# METEOR2K17_final.net
KiCad netlist of a schematic drawn in EAGLE
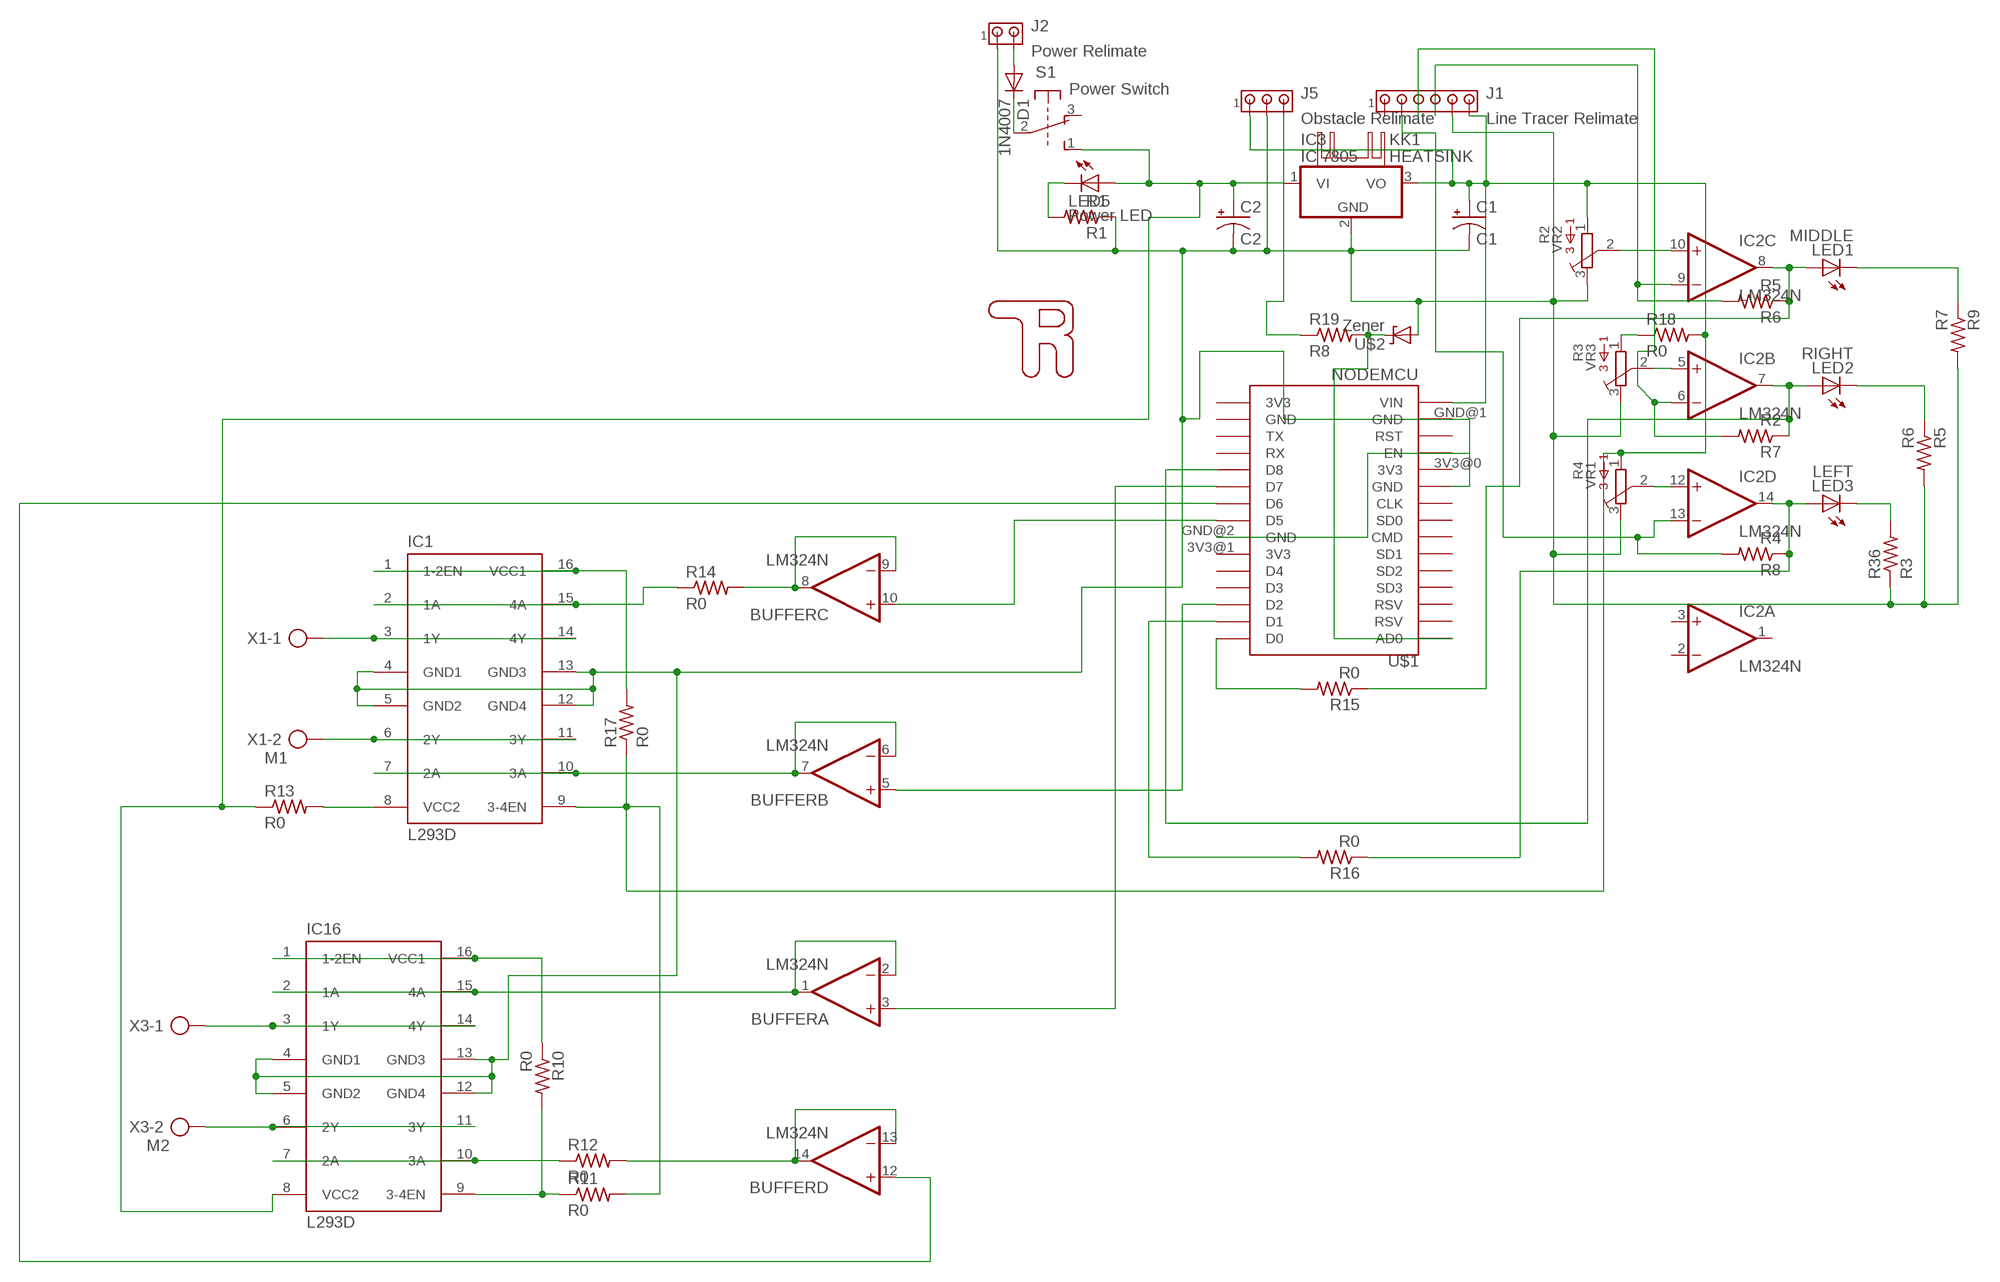
[diagram p0: schematic, sheet 1]

(export (version "E")
  (design (tool "Eeschema 10.0.6"))
  (components
    (comp (ref "BUFFER")
      (value "LM324N")
      (footprint "eagle-import:DIL14")
      (libsource (lib "eagle-import") (part "LM324N"))
    )
    (comp (ref "C1")
      (value "C1")
      (footprint "eagle-import:CPOL-RADIAL-5MM-10MM")
      (libsource (lib "eagle-import") (part "1000UF-RADIAL-5MM-25V-20%"))
    )
    (comp (ref "C2")
      (value "C2")
      (footprint "eagle-import:E3,5-8")
      (libsource (lib "eagle-import") (part "CPOL-USE3.5-8"))
    )
    (comp (ref "D1")
      (value "1N4007")
      (footprint "eagle-import:DO41-10")
      (libsource (lib "eagle-import") (part "1N4004"))
    )
    (comp (ref "IC1")
      (value "L293D")
      (footprint "eagle-import:DIL16")
      (libsource (lib "eagle-import") (part "L293D"))
    )
    (comp (ref "IC2")
      (value "LM324N")
      (footprint "eagle-import:DIL14")
      (libsource (lib "eagle-import") (part "LM324N"))
    )
    (comp (ref "IC3")
      (value "IC 7805")
      (footprint "eagle-import:TO220V")
      (libsource (lib "eagle-import") (part "78TV05"))
    )
    (comp (ref "IC16")
      (value "L293D")
      (footprint "eagle-import:DIL16")
      (libsource (lib "eagle-import") (part "L293D"))
    )
    (comp (ref "J1")
      (value "Line Tracer Relimate")
      (footprint "eagle-import:10X06MTA")
      (libsource (lib "eagle-import") (part "MTA06-100"))
    )
    (comp (ref "J2")
      (value "Power Relimate")
      (footprint "eagle-import:10X02MTA")
      (libsource (lib "eagle-import") (part "MTA02-100"))
    )
    (comp (ref "J5")
      (value "Obstacle Relimate")
      (footprint "eagle-import:10X03MTA")
      (libsource (lib "eagle-import") (part "MTA03-100"))
    )
    (comp (ref "KK1")
      (value "HEATSINK")
      (footprint "eagle-import:HEATSINK")
      (libsource (lib "eagle-import") (part "HEATSINK"))
    )
    (comp (ref "LED1")
      (value "MIDDLE")
      (footprint "eagle-import:LED3MM")
      (libsource (lib "eagle-import") (part "LED3MM"))
    )
    (comp (ref "LED2")
      (value "RIGHT")
      (footprint "eagle-import:LED3MM")
      (libsource (lib "eagle-import") (part "LED3MM"))
    )
    (comp (ref "LED3")
      (value "LEFT")
      (footprint "eagle-import:LED3MM")
      (libsource (lib "eagle-import") (part "LED3MM"))
    )
    (comp (ref "LED5")
      (value "Power LED")
      (footprint "eagle-import:LED3MM")
      (libsource (lib "eagle-import") (part "LED3MM"))
    )
    (comp (ref "R1")
      (value "R1")
      (footprint "eagle-import:0204_7")
      (libsource (lib "eagle-import") (part "R-US_0204/7"))
    )
    (comp (ref "R2")
      (value "VR2")
      (footprint "eagle-import:3386W")
      (libsource (lib "eagle-import") (part "3386-W"))
    )
    (comp (ref "R3")
      (value "VR3")
      (footprint "eagle-import:3386W")
      (libsource (lib "eagle-import") (part "3386-W"))
    )
    (comp (ref "R4")
      (value "VR1")
      (footprint "eagle-import:3386W")
      (libsource (lib "eagle-import") (part "3386-W"))
    )
    (comp (ref "R5")
      (value "R6")
      (footprint "eagle-import:0204_7")
      (libsource (lib "eagle-import") (part "R-US_0204/7"))
    )
    (comp (ref "R6")
      (value "R5")
      (footprint "eagle-import:0204_7")
      (libsource (lib "eagle-import") (part "R-US_0204/7"))
    )
    (comp (ref "R7")
      (value "R2")
      (footprint "eagle-import:0204_7")
      (libsource (lib "eagle-import") (part "R-US_0204/7"))
    )
    (comp (ref "R8")
      (value "R4")
      (footprint "eagle-import:0204_7")
      (libsource (lib "eagle-import") (part "R-US_0204/7"))
    )
    (comp (ref "R9")
      (value "R7")
      (footprint "eagle-import:0204_7")
      (libsource (lib "eagle-import") (part "R-US_0204/7"))
    )
    (comp (ref "R10")
      (value "R0")
      (footprint "eagle-import:0204_7")
      (libsource (lib "eagle-import") (part "R-US_0204/7"))
    )
    (comp (ref "R11")
      (value "R0")
      (footprint "eagle-import:0204_7")
      (libsource (lib "eagle-import") (part "R-US_0204/7"))
    )
    (comp (ref "R12")
      (value "R0")
      (footprint "eagle-import:0207_10")
      (libsource (lib "eagle-import") (part "R-US_0207/10"))
    )
    (comp (ref "R13")
      (value "R0")
      (footprint "eagle-import:0204_7")
      (libsource (lib "eagle-import") (part "R-US_0204/7"))
    )
    (comp (ref "R14")
      (value "R0")
      (footprint "eagle-import:0207_12")
      (libsource (lib "eagle-import") (part "R-US_0207/12"))
    )
    (comp (ref "R15")
      (value "R0")
      (footprint "eagle-import:0204_7")
      (libsource (lib "eagle-import") (part "R-US_0204/7"))
    )
    (comp (ref "R16")
      (value "R0")
      (footprint "eagle-import:0204_7")
      (libsource (lib "eagle-import") (part "R-US_0204/7"))
    )
    (comp (ref "R17")
      (value "R0")
      (footprint "eagle-import:0204_7")
      (libsource (lib "eagle-import") (part "R-US_0204/7"))
    )
    (comp (ref "R18")
      (value "R0")
      (footprint "eagle-import:0204_7")
      (libsource (lib "eagle-import") (part "R-US_0204/7"))
    )
    (comp (ref "R19")
      (value "R8")
      (footprint "eagle-import:0204_7")
      (libsource (lib "eagle-import") (part "R-US_0204/7"))
    )
    (comp (ref "R36")
      (value "R3")
      (footprint "eagle-import:0204_7")
      (libsource (lib "eagle-import") (part "R-US_0204/7"))
    )
    (comp (ref "S1")
      (value "Power Switch")
      (footprint "eagle-import:9077-2")
      (libsource (lib "eagle-import") (part "9077-2"))
    )
    (comp (ref "U$1")
      (value "NODEMCU")
      (footprint "eagle-import:NODEMCU_HSILK")
      (libsource (lib "eagle-import") (part "NODEMCU_V20"))
    )
    (comp (ref "U$2")
      (value "Zener")
      (footprint "eagle-import:DIODE-ZENER")
      (libsource (lib "eagle-import") (part "DIODE-ZENERPTH"))
    )
    (comp (ref "U$3")
      (value "TRLOGO")
      (footprint "eagle-import:TRLOGO")
      (libsource (lib "eagle-import") (part "TRLOGO"))
    )
    (comp (ref "X1")
      (value "M1")
      (footprint "eagle-import:AK300_2")
      (libsource (lib "eagle-import") (part "AK300/2"))
    )
    (comp (ref "X3")
      (value "M2")
      (footprint "eagle-import:AK300_2")
      (libsource (lib "eagle-import") (part "AK300/2"))
    )
  )
  (nets
    (net (code "1") (name "/5V") (class "Default")
      (node (ref "C1") (pin "+") (pinfunction "+_+") (pintype "passive"))
      (node (ref "IC1") (pin "1") (pinfunction "1-2EN_1") (pintype "input"))
      (node (ref "IC1") (pin "16") (pinfunction "VCC1_16") (pintype "power_in"))
      (node (ref "IC1") (pin "9") (pinfunction "3-4EN_9") (pintype "input"))
      (node (ref "IC16") (pin "1") (pinfunction "1-2EN_1") (pintype "input"))
      (node (ref "IC16") (pin "16") (pinfunction "VCC1_16") (pintype "power_in"))
      (node (ref "IC16") (pin "9") (pinfunction "3-4EN_9") (pintype "input"))
      (node (ref "IC3") (pin "3") (pinfunction "VO_3") (pintype "passive"))
      (node (ref "J1") (pin "1") (pinfunction "6_1") (pintype "passive"))
      (node (ref "J5") (pin "1") (pinfunction "1_1") (pintype "passive"))
      (node (ref "R10") (pin "1") (pinfunction "1_1") (pintype "passive"))
      (node (ref "R10") (pin "2") (pinfunction "2_2") (pintype "passive"))
      (node (ref "R11") (pin "1") (pinfunction "1_1") (pintype "passive"))
      (node (ref "R11") (pin "2") (pinfunction "2_2") (pintype "passive"))
      (node (ref "R17") (pin "1") (pinfunction "1_1") (pintype "passive"))
      (node (ref "R17") (pin "2") (pinfunction "2_2") (pintype "passive"))
      (node (ref "R18") (pin "2") (pinfunction "2_2") (pintype "passive"))
      (node (ref "R2") (pin "1") (pinfunction "1_1") (pintype "passive"))
      (node (ref "R4") (pin "1") (pinfunction "1_1") (pintype "passive"))
      (node (ref "U$1") (pin "VIN") (pinfunction "VIN_VIN") (pintype "bidirectional"))
    )
    (net (code "2") (name "/12V") (class "Default")
      (node (ref "C2") (pin "+") (pinfunction "+_+") (pintype "passive"))
      (node (ref "IC1") (pin "8") (pinfunction "VCC2_8") (pintype "power_in"))
      (node (ref "IC16") (pin "8") (pinfunction "VCC2_8") (pintype "power_in"))
      (node (ref "IC3") (pin "1") (pinfunction "VI_1") (pintype "input"))
      (node (ref "LED5") (pin "A") (pinfunction "A_A") (pintype "passive"))
      (node (ref "R13") (pin "1") (pinfunction "1_1") (pintype "passive"))
      (node (ref "R13") (pin "2") (pinfunction "2_2") (pintype "passive"))
      (node (ref "S1") (pin "1") (pinfunction "S_1") (pintype "passive"))
    )
    (net (code "3") (name "Net-(BUFFERA-+IN)") (class "Default")
      (node (ref "BUFFER") (pin "3") (pinfunction "+IN_3") (pintype "input"))
      (node (ref "U$1") (pin "D7") (pinfunction "D7_D7") (pintype "bidirectional"))
    )
    (net (code "4") (name "Net-(BUFFERA--IN)") (class "Default")
      (node (ref "BUFFER") (pin "1") (pinfunction "OUT_1") (pintype "output"))
      (node (ref "BUFFER") (pin "2") (pinfunction "-IN_2") (pintype "input"))
      (node (ref "IC16") (pin "15") (pinfunction "4A_15") (pintype "input"))
      (node (ref "IC16") (pin "2") (pinfunction "1A_2") (pintype "input"))
    )
    (net (code "5") (name "Net-(BUFFERB-+IN)") (class "Default")
      (node (ref "BUFFER") (pin "5") (pinfunction "+IN_5") (pintype "input"))
      (node (ref "U$1") (pin "D2") (pinfunction "D2_D2") (pintype "bidirectional"))
    )
    (net (code "6") (name "Net-(BUFFERB--IN)") (class "Default")
      (node (ref "BUFFER") (pin "6") (pinfunction "-IN_6") (pintype "input"))
      (node (ref "BUFFER") (pin "7") (pinfunction "OUT_7") (pintype "output"))
      (node (ref "IC1") (pin "10") (pinfunction "3A_10") (pintype "input"))
      (node (ref "IC1") (pin "7") (pinfunction "2A_7") (pintype "input"))
    )
    (net (code "7") (name "Net-(BUFFERC-+IN)") (class "Default")
      (node (ref "BUFFER") (pin "10") (pinfunction "+IN_10") (pintype "input"))
      (node (ref "U$1") (pin "D5") (pinfunction "D5_D5") (pintype "bidirectional"))
    )
    (net (code "8") (name "Net-(BUFFERC--IN)") (class "Default")
      (node (ref "BUFFER") (pin "8") (pinfunction "OUT_8") (pintype "output"))
      (node (ref "BUFFER") (pin "9") (pinfunction "-IN_9") (pintype "input"))
      (node (ref "R14") (pin "2") (pinfunction "2_2") (pintype "passive"))
    )
    (net (code "9") (name "Net-(BUFFERD-+IN)") (class "Default")
      (node (ref "BUFFER") (pin "12") (pinfunction "+IN_12") (pintype "input"))
      (node (ref "U$1") (pin "D6") (pinfunction "D6_D6") (pintype "bidirectional"))
    )
    (net (code "10") (name "Net-(BUFFERD--IN)") (class "Default")
      (node (ref "BUFFER") (pin "13") (pinfunction "-IN_13") (pintype "input"))
      (node (ref "BUFFER") (pin "14") (pinfunction "OUT_14") (pintype "output"))
      (node (ref "R12") (pin "2") (pinfunction "2_2") (pintype "passive"))
    )
    (net (code "11") (name "Net-(D1-PadA)") (class "Default")
      (node (ref "D1") (pin "A") (pinfunction "A_A") (pintype "passive"))
      (node (ref "J2") (pin "2") (pinfunction "2_2") (pintype "passive"))
    )
    (net (code "12") (name "Net-(IC1-1A)") (class "Default")
      (node (ref "IC1") (pin "15") (pinfunction "4A_15") (pintype "input"))
      (node (ref "IC1") (pin "2") (pinfunction "1A_2") (pintype "input"))
      (node (ref "R14") (pin "1") (pinfunction "1_1") (pintype "passive"))
    )
    (net (code "13") (name "Net-(IC1-1Y)") (class "Default")
      (node (ref "IC1") (pin "14") (pinfunction "4Y_14") (pintype "output"))
      (node (ref "IC1") (pin "3") (pinfunction "1Y_3") (pintype "output"))
      (node (ref "X1") (pin "1") (pinfunction "KL_1") (pintype "passive"))
    )
    (net (code "14") (name "Net-(IC1-2Y)") (class "Default")
      (node (ref "IC1") (pin "11") (pinfunction "3Y_11") (pintype "output"))
      (node (ref "IC1") (pin "6") (pinfunction "2Y_6") (pintype "output"))
      (node (ref "X1") (pin "2") (pinfunction "KL_2") (pintype "passive"))
    )
    (net (code "15") (name "Net-(IC1-GND1)") (class "Default")
      (node (ref "C1") (pin "-") (pinfunction "-_-") (pintype "passive"))
      (node (ref "C2") (pin "-") (pinfunction "-_-") (pintype "passive"))
      (node (ref "IC1") (pin "12") (pinfunction "GND4_12") (pintype "power_in"))
      (node (ref "IC1") (pin "13") (pinfunction "GND3_13") (pintype "power_in"))
      (node (ref "IC1") (pin "4") (pinfunction "GND1_4") (pintype "power_in"))
      (node (ref "IC1") (pin "5") (pinfunction "GND2_5") (pintype "power_in"))
      (node (ref "IC16") (pin "12") (pinfunction "GND4_12") (pintype "power_in"))
      (node (ref "IC16") (pin "13") (pinfunction "GND3_13") (pintype "power_in"))
      (node (ref "IC16") (pin "4") (pinfunction "GND1_4") (pintype "power_in"))
      (node (ref "IC16") (pin "5") (pinfunction "GND2_5") (pintype "power_in"))
      (node (ref "IC3") (pin "2") (pinfunction "GND_2") (pintype "passive"))
      (node (ref "J1") (pin "2") (pinfunction "5_2") (pintype "passive"))
      (node (ref "J2") (pin "1") (pinfunction "1_1") (pintype "passive"))
      (node (ref "J5") (pin "2") (pinfunction "2_2") (pintype "passive"))
      (node (ref "R1") (pin "1") (pinfunction "1_1") (pintype "passive"))
      (node (ref "R2") (pin "3") (pinfunction "3_3") (pintype "passive"))
      (node (ref "R3") (pin "3") (pinfunction "3_3") (pintype "passive"))
      (node (ref "R36") (pin "1") (pinfunction "1_1") (pintype "passive"))
      (node (ref "R4") (pin "3") (pinfunction "3_3") (pintype "passive"))
      (node (ref "R5") (pin "2") (pinfunction "2_2") (pintype "passive"))
      (node (ref "R9") (pin "2") (pinfunction "2_2") (pintype "passive"))
      (node (ref "U$1") (pin "GND@0") (pinfunction "GND_GND@0") (pintype "bidirectional"))
      (node (ref "U$1") (pin "GND@2") (pinfunction "GND_GND@2") (pintype "bidirectional"))
      (node (ref "U$2") (pin "P$2") (pinfunction "A_P$2") (pintype "passive"))
    )
    (net (code "16") (name "Net-(IC2B-+IN)") (class "Default")
      (node (ref "IC2") (pin "5") (pinfunction "+IN_5") (pintype "input"))
      (node (ref "R3") (pin "2") (pinfunction "2_2") (pintype "passive"))
    )
    (net (code "17") (name "Net-(IC2B--IN)") (class "Default")
      (node (ref "IC2") (pin "6") (pinfunction "-IN_6") (pintype "input"))
      (node (ref "J1") (pin "4") (pinfunction "3_4") (pintype "passive"))
      (node (ref "R7") (pin "2") (pinfunction "2_2") (pintype "passive"))
    )
    (net (code "18") (name "Net-(IC2B-OUT)") (class "Default")
      (node (ref "IC2") (pin "7") (pinfunction "OUT_7") (pintype "output"))
      (node (ref "LED2") (pin "A") (pinfunction "A_A") (pintype "passive"))
      (node (ref "R7") (pin "1") (pinfunction "1_1") (pintype "passive"))
      (node (ref "U$1") (pin "D8") (pinfunction "D8_D8") (pintype "bidirectional"))
    )
    (net (code "19") (name "Net-(IC2C-+IN)") (class "Default")
      (node (ref "IC2") (pin "10") (pinfunction "+IN_10") (pintype "input"))
      (node (ref "R2") (pin "2") (pinfunction "2_2") (pintype "passive"))
    )
    (net (code "20") (name "Net-(IC2C--IN)") (class "Default")
      (node (ref "IC2") (pin "9") (pinfunction "-IN_9") (pintype "input"))
      (node (ref "J1") (pin "3") (pinfunction "4_3") (pintype "passive"))
      (node (ref "R6") (pin "2") (pinfunction "2_2") (pintype "passive"))
    )
    (net (code "21") (name "Net-(IC2C-OUT)") (class "Default")
      (node (ref "IC2") (pin "8") (pinfunction "OUT_8") (pintype "output"))
      (node (ref "LED1") (pin "A") (pinfunction "A_A") (pintype "passive"))
      (node (ref "R15") (pin "1") (pinfunction "1_1") (pintype "passive"))
      (node (ref "R6") (pin "1") (pinfunction "1_1") (pintype "passive"))
    )
    (net (code "22") (name "Net-(IC2D-+IN)") (class "Default")
      (node (ref "IC2") (pin "12") (pinfunction "+IN_12") (pintype "input"))
      (node (ref "R4") (pin "2") (pinfunction "2_2") (pintype "passive"))
    )
    (net (code "23") (name "Net-(IC2D--IN)") (class "Default")
      (node (ref "IC2") (pin "13") (pinfunction "-IN_13") (pintype "input"))
      (node (ref "J1") (pin "5") (pinfunction "2_5") (pintype "passive"))
      (node (ref "R8") (pin "2") (pinfunction "2_2") (pintype "passive"))
    )
    (net (code "24") (name "Net-(IC2D-OUT)") (class "Default")
      (node (ref "IC2") (pin "14") (pinfunction "OUT_14") (pintype "output"))
      (node (ref "LED3") (pin "A") (pinfunction "A_A") (pintype "passive"))
      (node (ref "R16") (pin "1") (pinfunction "1_1") (pintype "passive"))
      (node (ref "R8") (pin "1") (pinfunction "1_1") (pintype "passive"))
    )
    (net (code "25") (name "Net-(IC16-1Y)") (class "Default")
      (node (ref "IC16") (pin "14") (pinfunction "4Y_14") (pintype "output"))
      (node (ref "IC16") (pin "3") (pinfunction "1Y_3") (pintype "output"))
      (node (ref "X3") (pin "1") (pinfunction "KL_1") (pintype "passive"))
    )
    (net (code "26") (name "Net-(IC16-2A)") (class "Default")
      (node (ref "IC16") (pin "10") (pinfunction "3A_10") (pintype "input"))
      (node (ref "IC16") (pin "7") (pinfunction "2A_7") (pintype "input"))
      (node (ref "R12") (pin "1") (pinfunction "1_1") (pintype "passive"))
    )
    (net (code "27") (name "Net-(IC16-2Y)") (class "Default")
      (node (ref "IC16") (pin "11") (pinfunction "3Y_11") (pintype "output"))
      (node (ref "IC16") (pin "6") (pinfunction "2Y_6") (pintype "output"))
      (node (ref "X3") (pin "2") (pinfunction "KL_2") (pintype "passive"))
    )
    (net (code "28") (name "Net-(J5-Pad3)") (class "Default")
      (node (ref "J5") (pin "3") (pinfunction "3_3") (pintype "passive"))
      (node (ref "R19") (pin "1") (pinfunction "1_1") (pintype "passive"))
    )
    (net (code "29") (name "Net-(LED1-C)") (class "Default")
      (node (ref "LED1") (pin "K") (pinfunction "C_K") (pintype "passive"))
      (node (ref "R9") (pin "1") (pinfunction "1_1") (pintype "passive"))
    )
    (net (code "30") (name "Net-(LED2-C)") (class "Default")
      (node (ref "LED2") (pin "K") (pinfunction "C_K") (pintype "passive"))
      (node (ref "R5") (pin "1") (pinfunction "1_1") (pintype "passive"))
    )
    (net (code "31") (name "Net-(LED3-C)") (class "Default")
      (node (ref "LED3") (pin "K") (pinfunction "C_K") (pintype "passive"))
      (node (ref "R36") (pin "2") (pinfunction "2_2") (pintype "passive"))
    )
    (net (code "32") (name "Net-(LED5-C)") (class "Default")
      (node (ref "LED5") (pin "K") (pinfunction "C_K") (pintype "passive"))
      (node (ref "R1") (pin "2") (pinfunction "2_2") (pintype "passive"))
    )
    (net (code "33") (name "Net-(R15-Pad2)") (class "Default")
      (node (ref "R15") (pin "2") (pinfunction "2_2") (pintype "passive"))
      (node (ref "U$1") (pin "D0") (pinfunction "D0_D0") (pintype "bidirectional"))
    )
    (net (code "34") (name "Net-(R16-Pad2)") (class "Default")
      (node (ref "R16") (pin "2") (pinfunction "2_2") (pintype "passive"))
      (node (ref "U$1") (pin "D1") (pinfunction "D1_D1") (pintype "bidirectional"))
    )
    (net (code "35") (name "Net-(R18-Pad1)") (class "Default")
      (node (ref "R18") (pin "1") (pinfunction "1_1") (pintype "passive"))
      (node (ref "R3") (pin "1") (pinfunction "1_1") (pintype "passive"))
    )
    (net (code "36") (name "Net-(S1A-P)") (class "Default")
      (node (ref "D1") (pin "C") (pinfunction "C_C") (pintype "passive"))
      (node (ref "S1") (pin "2") (pinfunction "P_2") (pintype "passive"))
    )
    (net (code "37") (name "Net-(U$2-C)") (class "Default")
      (node (ref "R19") (pin "2") (pinfunction "2_2") (pintype "passive"))
      (node (ref "U$1") (pin "AD0") (pinfunction "AD0_AD0") (pintype "bidirectional"))
      (node (ref "U$2") (pin "P$1") (pinfunction "C_P$1") (pintype "passive"))
    )
    (net (code "38") (name "unconnected-(IC2A-+IN-Pad3)") (class "Default")
      (node (ref "IC2") (pin "3") (pinfunction "+IN_3") (pintype "input"))
    )
    (net (code "39") (name "unconnected-(IC2A--IN-Pad2)") (class "Default")
      (node (ref "IC2") (pin "2") (pinfunction "-IN_2") (pintype "input"))
    )
    (net (code "40") (name "unconnected-(IC2A-OUT-Pad1)") (class "Default")
      (node (ref "IC2") (pin "1") (pinfunction "OUT_1") (pintype "output"))
    )
    (net (code "41") (name "unconnected-(J1-1-Pad6)") (class "Default")
      (node (ref "J1") (pin "6") (pinfunction "1_6") (pintype "passive"))
    )
    (net (code "42") (name "unconnected-(S1A-O-Pad3)") (class "Default")
      (node (ref "S1") (pin "3") (pinfunction "O_3") (pintype "passive"))
    )
    (net (code "43") (name "unconnected-(U$1-3V3-Pad3V3@0)") (class "Default")
      (node (ref "U$1") (pin "3V3@0") (pinfunction "3V3_3V3@0") (pintype "bidirectional"))
    )
    (net (code "44") (name "unconnected-(U$1-3V3-Pad3V3@1)") (class "Default")
      (node (ref "U$1") (pin "3V3@1") (pinfunction "3V3_3V3@1") (pintype "bidirectional"))
    )
    (net (code "45") (name "unconnected-(U$1-3V3-Pad3V3@2)") (class "Default")
      (node (ref "U$1") (pin "3V3@2") (pinfunction "3V3_3V3@2") (pintype "bidirectional"))
    )
    (net (code "46") (name "unconnected-(U$1-GND-PadGND@1)") (class "Default")
      (node (ref "U$1") (pin "GND@1") (pinfunction "GND_GND@1") (pintype "bidirectional"))
    )
    (net (code "47") (name "unconnected-(U$1-GND-PadGND@3)") (class "Default")
      (node (ref "U$1") (pin "GND@3") (pinfunction "GND_GND@3") (pintype "bidirectional"))
    )
    (net (code "48") (name "unconnected-(U$1-PadCLK)") (class "Default")
      (node (ref "U$1") (pin "CLK") (pinfunction "CLK_CLK") (pintype "bidirectional"))
    )
    (net (code "49") (name "unconnected-(U$1-PadCMD)") (class "Default")
      (node (ref "U$1") (pin "CMD") (pinfunction "CMD_CMD") (pintype "bidirectional"))
    )
    (net (code "50") (name "unconnected-(U$1-PadD3)") (class "Default")
      (node (ref "U$1") (pin "D3") (pinfunction "D3_D3") (pintype "bidirectional"))
    )
    (net (code "51") (name "unconnected-(U$1-PadD4)") (class "Default")
      (node (ref "U$1") (pin "D4") (pinfunction "D4_D4") (pintype "bidirectional"))
    )
    (net (code "52") (name "unconnected-(U$1-PadEN)") (class "Default")
      (node (ref "U$1") (pin "EN") (pinfunction "EN_EN") (pintype "bidirectional"))
    )
    (net (code "53") (name "unconnected-(U$1-PadRST)") (class "Default")
      (node (ref "U$1") (pin "RST") (pinfunction "RST_RST") (pintype "bidirectional"))
    )
    (net (code "54") (name "unconnected-(U$1-PadRX)") (class "Default")
      (node (ref "U$1") (pin "RX") (pinfunction "RX_RX") (pintype "bidirectional"))
    )
    (net (code "55") (name "unconnected-(U$1-PadSD0)") (class "Default")
      (node (ref "U$1") (pin "SD0") (pinfunction "SD0_SD0") (pintype "bidirectional"))
    )
    (net (code "56") (name "unconnected-(U$1-PadSD1)") (class "Default")
      (node (ref "U$1") (pin "SD1") (pinfunction "SD1_SD1") (pintype "bidirectional"))
    )
    (net (code "57") (name "unconnected-(U$1-PadSD2)") (class "Default")
      (node (ref "U$1") (pin "SD2") (pinfunction "SD2_SD2") (pintype "bidirectional"))
    )
    (net (code "58") (name "unconnected-(U$1-PadSD3)") (class "Default")
      (node (ref "U$1") (pin "SD3") (pinfunction "SD3_SD3") (pintype "bidirectional"))
    )
    (net (code "59") (name "unconnected-(U$1-PadTX)") (class "Default")
      (node (ref "U$1") (pin "TX") (pinfunction "TX_TX") (pintype "bidirectional"))
    )
    (net (code "60") (name "unconnected-(U$1-RSV-PadRSV@0)") (class "Default")
      (node (ref "U$1") (pin "RSV@0") (pinfunction "RSV_RSV@0") (pintype "bidirectional"))
    )
    (net (code "61") (name "unconnected-(U$1-RSV-PadRSV@1)") (class "Default")
      (node (ref "U$1") (pin "RSV@1") (pinfunction "RSV_RSV@1") (pintype "bidirectional"))
    )
  )
)
